# untitled.net
KiCad netlist of a schematic drawn in EAGLE
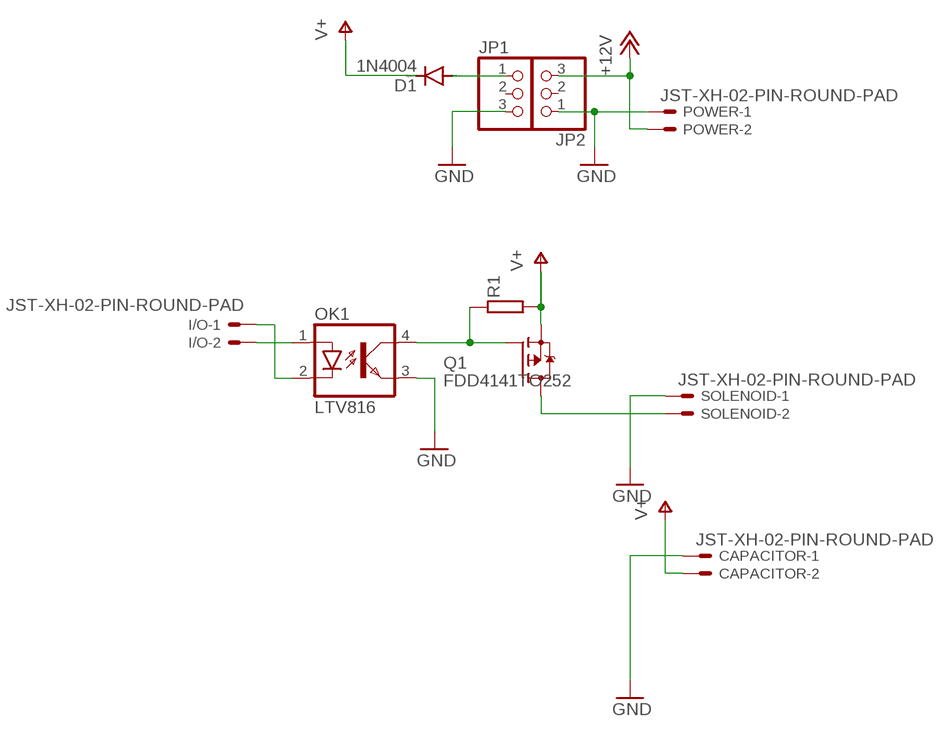
[diagram p0: schematic, sheet 1]

(export (version "E")
  (design (tool "Eeschema 10.0.6"))
  (components
    (comp (ref "CAPACITOR")
      (value "JST-XH-02-PIN-ROUND-PAD")
      (footprint "eagle-import:JST-XH-02-PACKAGE-ROUND-PAD")
      (libsource (lib "eagle-import") (part "JST-XH-02-PIN-ROUND-PAD"))
    )
    (comp (ref "D1")
      (value "1N4004")
      (footprint "eagle-import:DO41-10")
      (libsource (lib "eagle-import") (part "1N4004"))
    )
    (comp (ref "I/O")
      (value "JST-XH-02-PIN-ROUND-PAD")
      (footprint "eagle-import:JST-XH-02-PACKAGE-ROUND-PAD")
      (libsource (lib "eagle-import") (part "JST-XH-02-PIN-ROUND-PAD"))
    )
    (comp (ref "JP1")
      (value "PINHD-1X3")
      (footprint "eagle-import:1X03")
      (libsource (lib "eagle-import") (part "PINHD-1X3"))
    )
    (comp (ref "JP2")
      (value "PINHD-1X3")
      (footprint "eagle-import:1X03")
      (libsource (lib "eagle-import") (part "PINHD-1X3"))
    )
    (comp (ref "OK1")
      (value "LTV816")
      (footprint "eagle-import:DIL04")
      (libsource (lib "eagle-import") (part "LTV816"))
    )
    (comp (ref "POWER")
      (value "JST-XH-02-PIN-ROUND-PAD")
      (footprint "eagle-import:JST-XH-02-PACKAGE-ROUND-PAD")
      (libsource (lib "eagle-import") (part "JST-XH-02-PIN-ROUND-PAD"))
    )
    (comp (ref "Q1")
      (value "FDD4141TO252")
      (footprint "eagle-import:TO252")
      (libsource (lib "eagle-import") (part "FDD4141TO252"))
    )
    (comp (ref "R1")
      (value "RESISTOR1608")
      (footprint "eagle-import:SMD1608")
      (libsource (lib "eagle-import") (part "RESISTOR1608"))
    )
    (comp (ref "SOLENOID")
      (value "JST-XH-02-PIN-ROUND-PAD")
      (footprint "eagle-import:JST-XH-02-PACKAGE-ROUND-PAD")
      (libsource (lib "eagle-import") (part "JST-XH-02-PIN-ROUND-PAD"))
    )
  )
  (nets
    (net (code "1") (name "+12V") (class "Default")
      (node (ref "JP2") (pin "3") (pinfunction "3_3") (pintype "passive"))
      (node (ref "POWER") (pin "2") (pinfunction "S_2") (pintype "passive"))
    )
    (net (code "2") (name "GND") (class "Default")
      (node (ref "CAPACITOR") (pin "1") (pinfunction "S_1") (pintype "passive"))
      (node (ref "JP1") (pin "3") (pinfunction "3_3") (pintype "passive"))
      (node (ref "JP2") (pin "1") (pinfunction "1_1") (pintype "passive"))
      (node (ref "OK1") (pin "3") (pinfunction "EMIT_3") (pintype "passive"))
      (node (ref "POWER") (pin "1") (pinfunction "S_1") (pintype "passive"))
      (node (ref "SOLENOID") (pin "1") (pinfunction "S_1") (pintype "passive"))
    )
    (net (code "3") (name "Net-(D1-PadA)") (class "Default")
      (node (ref "D1") (pin "A") (pinfunction "A_A") (pintype "passive"))
      (node (ref "JP1") (pin "1") (pinfunction "1_1") (pintype "passive"))
    )
    (net (code "4") (name "Net-(I/OA-S)") (class "Default")
      (node (ref "I/O") (pin "1") (pinfunction "S_1") (pintype "passive"))
      (node (ref "OK1") (pin "2") (pinfunction "C_2") (pintype "passive"))
    )
    (net (code "5") (name "Net-(I/OB-S)") (class "Default")
      (node (ref "I/O") (pin "2") (pinfunction "S_2") (pintype "passive"))
      (node (ref "OK1") (pin "1") (pinfunction "A_1") (pintype "passive"))
    )
    (net (code "6") (name "Net-(OK1-COL)") (class "Default")
      (node (ref "OK1") (pin "4") (pinfunction "COL_4") (pintype "passive"))
      (node (ref "Q1") (pin "1") (pinfunction "G_1") (pintype "passive"))
      (node (ref "R1") (pin "1") (pinfunction "1_1") (pintype "passive"))
    )
    (net (code "7") (name "Net-(Q1-D)") (class "Default")
      (node (ref "Q1") (pin "3") (pinfunction "D_3") (pintype "passive"))
      (node (ref "SOLENOID") (pin "2") (pinfunction "S_2") (pintype "passive"))
    )
    (net (code "8") (name "V+") (class "Default")
      (node (ref "CAPACITOR") (pin "2") (pinfunction "S_2") (pintype "passive"))
      (node (ref "D1") (pin "C") (pinfunction "C_C") (pintype "passive"))
      (node (ref "Q1") (pin "2") (pinfunction "S_2") (pintype "passive"))
      (node (ref "R1") (pin "2") (pinfunction "2_2") (pintype "passive"))
    )
    (net (code "9") (name "unconnected-(JP1-Pad2)") (class "Default")
      (node (ref "JP1") (pin "2") (pinfunction "2_2") (pintype "passive"))
    )
    (net (code "10") (name "unconnected-(JP2-Pad2)") (class "Default")
      (node (ref "JP2") (pin "2") (pinfunction "2_2") (pintype "passive"))
    )
  )
)
